# comp.net
KiCad netlist of a schematic drawn in EAGLE
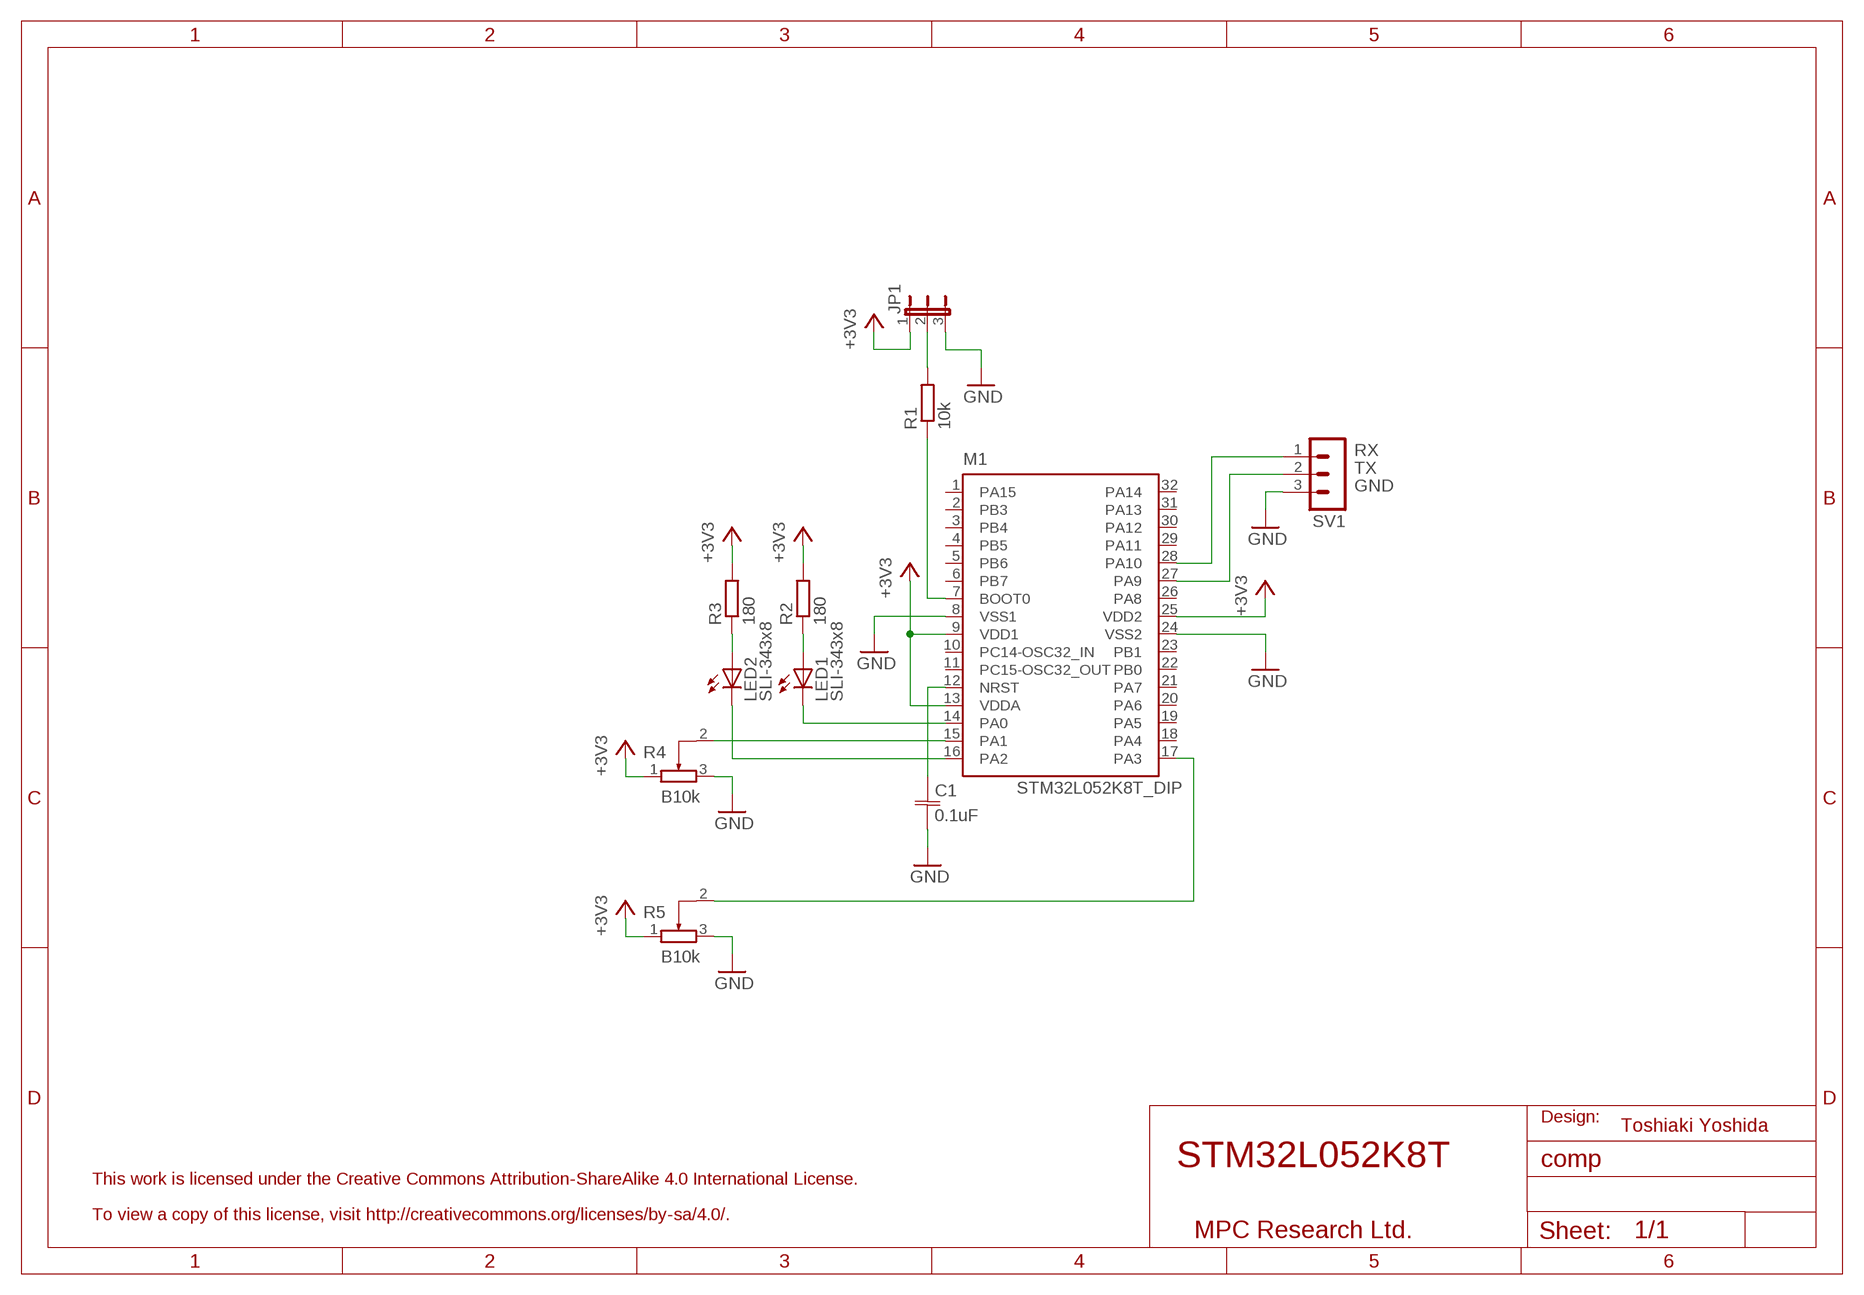
[diagram p0: schematic, sheet 1]

(export (version "E")
  (design (tool "Eeschema 10.0.6"))
  (components
    (comp (ref "C1")
      (value "0.1uF")
      (footprint "eagle-import:C050-024X044")
      (libsource (lib "eagle-import") (part "C-JIS050-024X044"))
    )
    (comp (ref "JP1")
      (value "JP2E")
      (footprint "eagle-import:JP2")
      (libsource (lib "eagle-import") (part "JP2E"))
    )
    (comp (ref "LED1")
      (value "SLI-343x8")
      (footprint "eagle-import:LED3MM")
      (libsource (lib "eagle-import") (part "LED3MM"))
    )
    (comp (ref "LED2")
      (value "SLI-343x8")
      (footprint "eagle-import:LED3MM")
      (libsource (lib "eagle-import") (part "LED3MM"))
    )
    (comp (ref "M1")
      (value "STM32L052K8T_DIP")
      (footprint "eagle-import:DIP32")
      (libsource (lib "eagle-import") (part "STM32L052K8T_DIP"))
    )
    (comp (ref "R1")
      (value "10k")
      (footprint "eagle-import:0207_2V")
      (libsource (lib "eagle-import") (part "R-EU_0207/2V"))
    )
    (comp (ref "R2")
      (value "180")
      (footprint "eagle-import:0207_2V")
      (libsource (lib "eagle-import") (part "R-EU_0207/2V"))
    )
    (comp (ref "R3")
      (value "180")
      (footprint "eagle-import:0207_2V")
      (libsource (lib "eagle-import") (part "R-EU_0207/2V"))
    )
    (comp (ref "R4")
      (value "B10k")
      (footprint "eagle-import:RK09L1140")
      (libsource (lib "eagle-import") (part "RK09L1140"))
    )
    (comp (ref "R5")
      (value "B10k")
      (footprint "eagle-import:RK09L1140")
      (libsource (lib "eagle-import") (part "RK09L1140"))
    )
    (comp (ref "SV1")
      (value "MA03-1")
      (footprint "eagle-import:MA03-1")
      (libsource (lib "eagle-import") (part "MA03-1"))
    )
  )
  (nets
    (net (code "1") (name "+3V3") (class "Default")
      (node (ref "JP1") (pin "1") (pinfunction "1_1") (pintype "passive"))
      (node (ref "M1") (pin "13") (pinfunction "VDDA_13") (pintype "power_in"))
      (node (ref "M1") (pin "25") (pinfunction "VDD2_25") (pintype "bidirectional"))
      (node (ref "M1") (pin "9") (pinfunction "VDD1_9") (pintype "power_in"))
      (node (ref "R2") (pin "2") (pinfunction "2_2") (pintype "passive"))
      (node (ref "R3") (pin "2") (pinfunction "2_2") (pintype "passive"))
      (node (ref "R4") (pin "1") (pinfunction "1_1") (pintype "passive"))
      (node (ref "R5") (pin "1") (pinfunction "1_1") (pintype "passive"))
    )
    (net (code "2") (name "GND") (class "Default")
      (node (ref "C1") (pin "2") (pinfunction "2_2") (pintype "passive"))
      (node (ref "JP1") (pin "3") (pinfunction "3_3") (pintype "passive"))
      (node (ref "M1") (pin "24") (pinfunction "VSS2_24") (pintype "power_in"))
      (node (ref "M1") (pin "8") (pinfunction "VSS1_8") (pintype "power_in"))
      (node (ref "R4") (pin "3") (pinfunction "3_3") (pintype "passive"))
      (node (ref "R5") (pin "3") (pinfunction "3_3") (pintype "passive"))
      (node (ref "SV1") (pin "3") (pinfunction "3_3") (pintype "passive"))
    )
    (net (code "3") (name "Net-(JP1-Pad2)") (class "Default")
      (node (ref "JP1") (pin "2") (pinfunction "2_2") (pintype "passive"))
      (node (ref "R1") (pin "2") (pinfunction "2_2") (pintype "passive"))
    )
    (net (code "4") (name "Net-(LED1-C)") (class "Default")
      (node (ref "LED1") (pin "K") (pinfunction "C_K") (pintype "passive"))
      (node (ref "M1") (pin "14") (pinfunction "PA0_14") (pintype "bidirectional"))
    )
    (net (code "5") (name "Net-(LED1-PadA)") (class "Default")
      (node (ref "LED1") (pin "A") (pinfunction "A_A") (pintype "passive"))
      (node (ref "R2") (pin "1") (pinfunction "1_1") (pintype "passive"))
    )
    (net (code "6") (name "Net-(LED2-C)") (class "Default")
      (node (ref "LED2") (pin "K") (pinfunction "C_K") (pintype "passive"))
      (node (ref "M1") (pin "16") (pinfunction "PA2_16") (pintype "bidirectional"))
    )
    (net (code "7") (name "Net-(LED2-PadA)") (class "Default")
      (node (ref "LED2") (pin "A") (pinfunction "A_A") (pintype "passive"))
      (node (ref "R3") (pin "1") (pinfunction "1_1") (pintype "passive"))
    )
    (net (code "8") (name "Net-(M1-BOOT0)") (class "Default")
      (node (ref "M1") (pin "7") (pinfunction "BOOT0_7") (pintype "bidirectional"))
      (node (ref "R1") (pin "1") (pinfunction "1_1") (pintype "passive"))
    )
    (net (code "9") (name "Net-(M1-NRST)") (class "Default")
      (node (ref "C1") (pin "1") (pinfunction "1_1") (pintype "passive"))
      (node (ref "M1") (pin "12") (pinfunction "NRST_12") (pintype "bidirectional"))
    )
    (net (code "10") (name "Net-(M1-PA1)") (class "Default")
      (node (ref "M1") (pin "15") (pinfunction "PA1_15") (pintype "bidirectional"))
      (node (ref "R4") (pin "2") (pinfunction "2_2") (pintype "passive"))
    )
    (net (code "11") (name "Net-(M1-PA3)") (class "Default")
      (node (ref "M1") (pin "17") (pinfunction "PA3_17") (pintype "bidirectional"))
      (node (ref "R5") (pin "2") (pinfunction "2_2") (pintype "passive"))
    )
    (net (code "12") (name "Net-(M1-PA9)") (class "Default")
      (node (ref "M1") (pin "27") (pinfunction "PA9_27") (pintype "bidirectional"))
      (node (ref "SV1") (pin "2") (pinfunction "2_2") (pintype "passive"))
    )
    (net (code "13") (name "Net-(M1-PA10)") (class "Default")
      (node (ref "M1") (pin "28") (pinfunction "PA10_28") (pintype "bidirectional"))
      (node (ref "SV1") (pin "1") (pinfunction "1_1") (pintype "passive"))
    )
    (net (code "14") (name "unconnected-(M1-PA4-Pad18)") (class "Default")
      (node (ref "M1") (pin "18") (pinfunction "PA4_18") (pintype "bidirectional"))
    )
    (net (code "15") (name "unconnected-(M1-PA5-Pad19)") (class "Default")
      (node (ref "M1") (pin "19") (pinfunction "PA5_19") (pintype "bidirectional"))
    )
    (net (code "16") (name "unconnected-(M1-PA6-Pad20)") (class "Default")
      (node (ref "M1") (pin "20") (pinfunction "PA6_20") (pintype "bidirectional"))
    )
    (net (code "17") (name "unconnected-(M1-PA7-Pad21)") (class "Default")
      (node (ref "M1") (pin "21") (pinfunction "PA7_21") (pintype "bidirectional"))
    )
    (net (code "18") (name "unconnected-(M1-PA8-Pad26)") (class "Default")
      (node (ref "M1") (pin "26") (pinfunction "PA8_26") (pintype "bidirectional"))
    )
    (net (code "19") (name "unconnected-(M1-PA11-Pad29)") (class "Default")
      (node (ref "M1") (pin "29") (pinfunction "PA11_29") (pintype "bidirectional"))
    )
    (net (code "20") (name "unconnected-(M1-PA12-Pad30)") (class "Default")
      (node (ref "M1") (pin "30") (pinfunction "PA12_30") (pintype "bidirectional"))
    )
    (net (code "21") (name "unconnected-(M1-PA13-Pad31)") (class "Default")
      (node (ref "M1") (pin "31") (pinfunction "PA13_31") (pintype "bidirectional"))
    )
    (net (code "22") (name "unconnected-(M1-PA14-Pad32)") (class "Default")
      (node (ref "M1") (pin "32") (pinfunction "PA14_32") (pintype "bidirectional"))
    )
    (net (code "23") (name "unconnected-(M1-PA15-Pad1)") (class "Default")
      (node (ref "M1") (pin "1") (pinfunction "PA15_1") (pintype "bidirectional"))
    )
    (net (code "24") (name "unconnected-(M1-PB0-Pad22)") (class "Default")
      (node (ref "M1") (pin "22") (pinfunction "PB0_22") (pintype "bidirectional"))
    )
    (net (code "25") (name "unconnected-(M1-PB1-Pad23)") (class "Default")
      (node (ref "M1") (pin "23") (pinfunction "PB1_23") (pintype "bidirectional"))
    )
    (net (code "26") (name "unconnected-(M1-PB3-Pad2)") (class "Default")
      (node (ref "M1") (pin "2") (pinfunction "PB3_2") (pintype "bidirectional"))
    )
    (net (code "27") (name "unconnected-(M1-PB4-Pad3)") (class "Default")
      (node (ref "M1") (pin "3") (pinfunction "PB4_3") (pintype "bidirectional"))
    )
    (net (code "28") (name "unconnected-(M1-PB5-Pad4)") (class "Default")
      (node (ref "M1") (pin "4") (pinfunction "PB5_4") (pintype "bidirectional"))
    )
    (net (code "29") (name "unconnected-(M1-PB6-Pad5)") (class "Default")
      (node (ref "M1") (pin "5") (pinfunction "PB6_5") (pintype "bidirectional"))
    )
    (net (code "30") (name "unconnected-(M1-PB7-Pad6)") (class "Default")
      (node (ref "M1") (pin "6") (pinfunction "PB7_6") (pintype "bidirectional"))
    )
    (net (code "31") (name "unconnected-(M1-PC14-OSC32_IN-Pad10)") (class "Default")
      (node (ref "M1") (pin "10") (pinfunction "PC14-OSC32_IN_10") (pintype "bidirectional"))
    )
    (net (code "32") (name "unconnected-(M1-PC15-OSC32_OUT-Pad11)") (class "Default")
      (node (ref "M1") (pin "11") (pinfunction "PC15-OSC32_OUT_11") (pintype "bidirectional"))
    )
  )
)
